# Finger_PPG.net
KiCad netlist of a schematic drawn in EAGLE
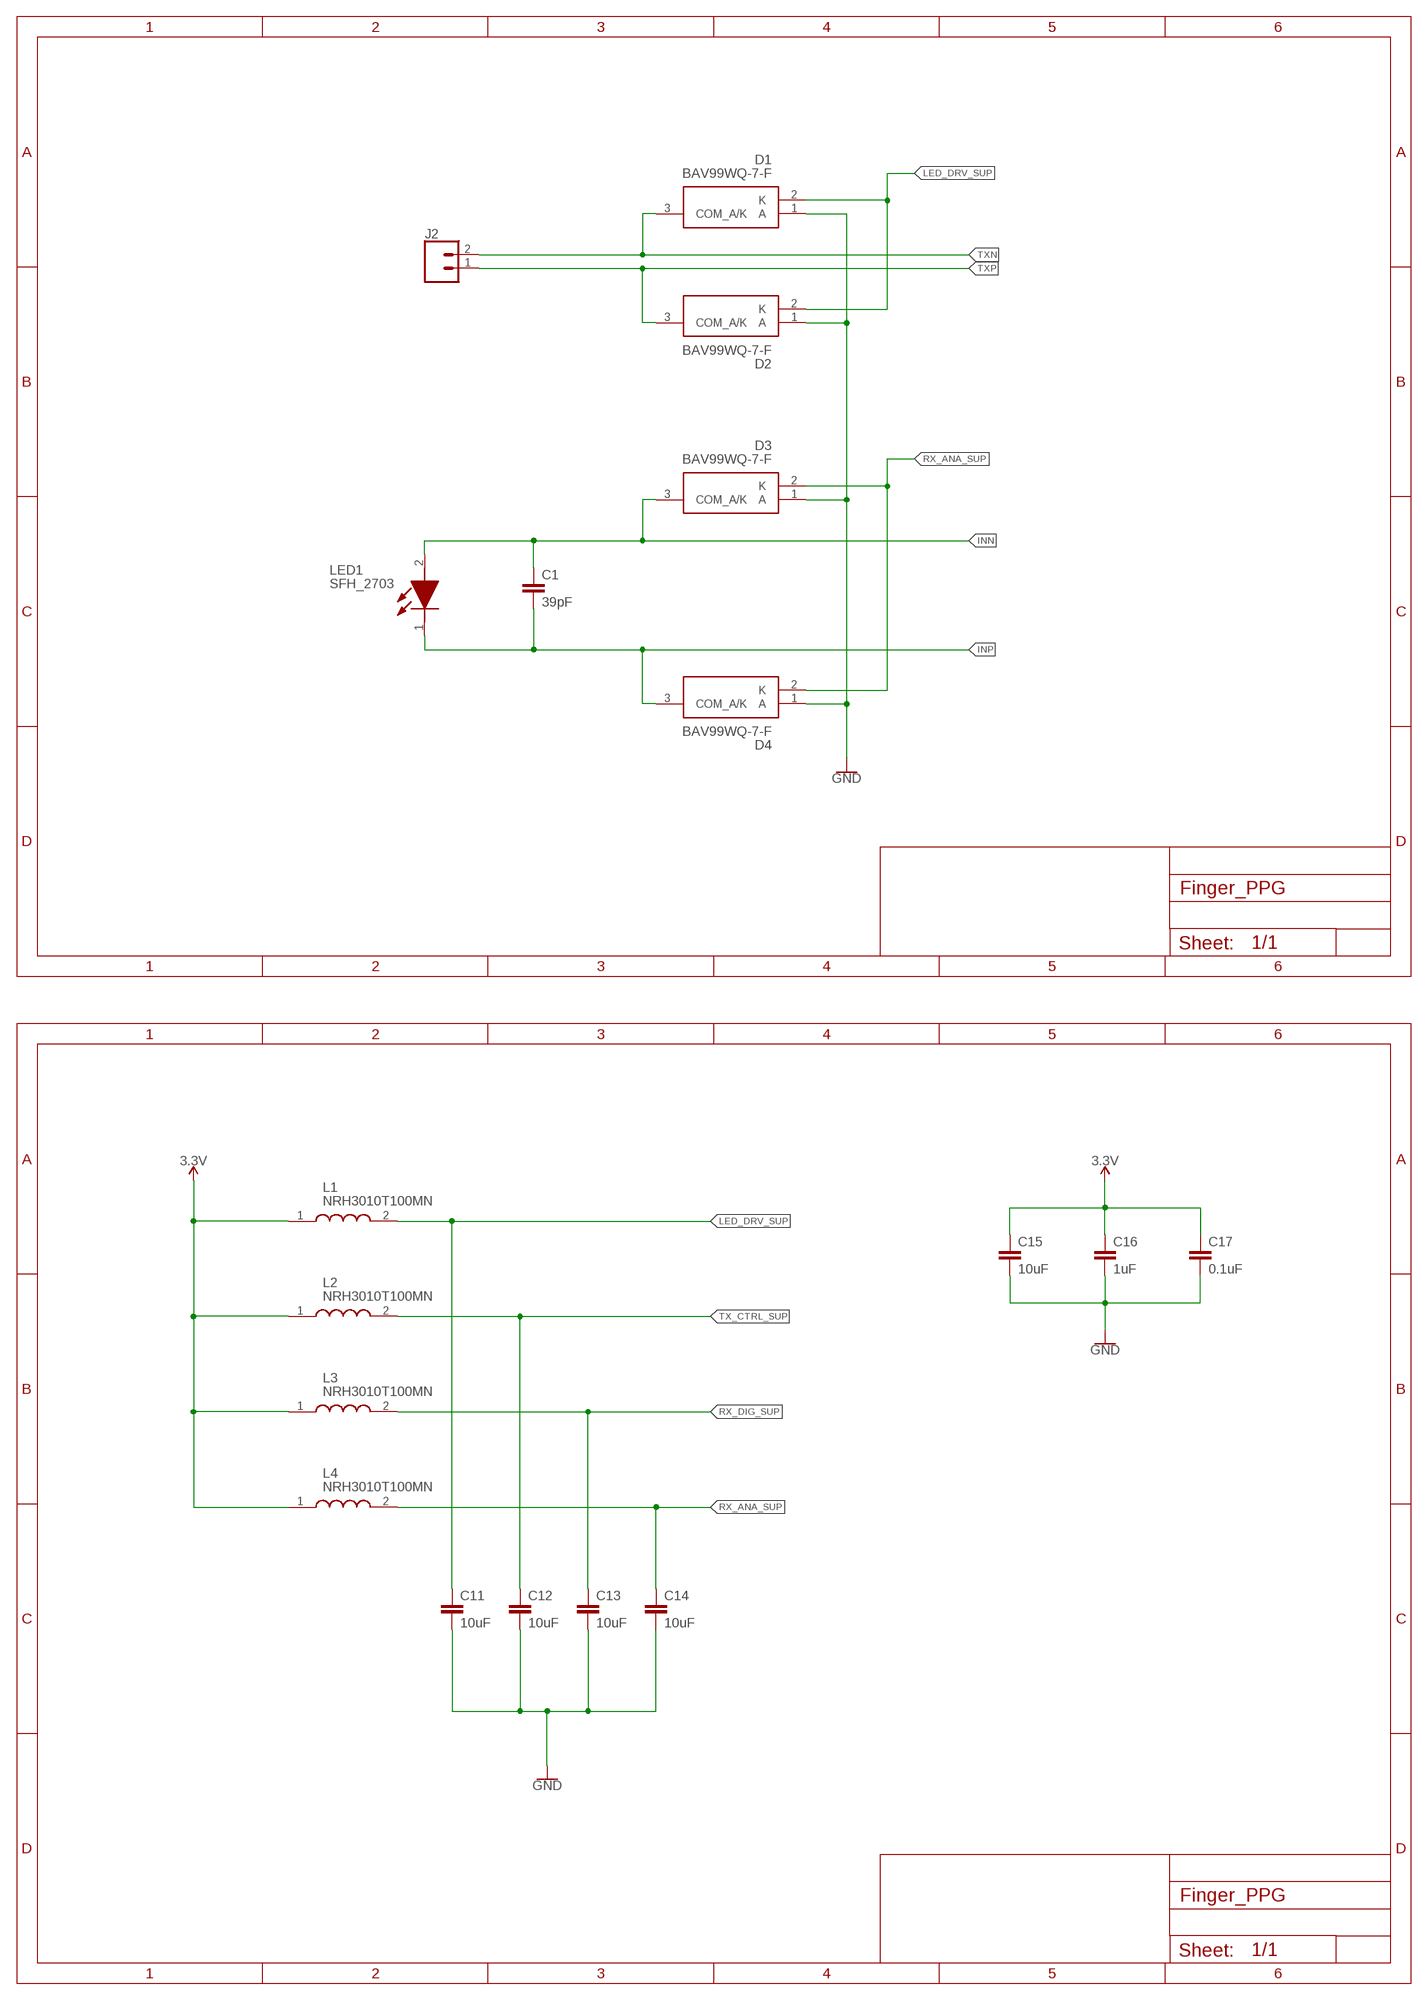
[diagram p0: schematic, sheet 1, part 1 of 2]
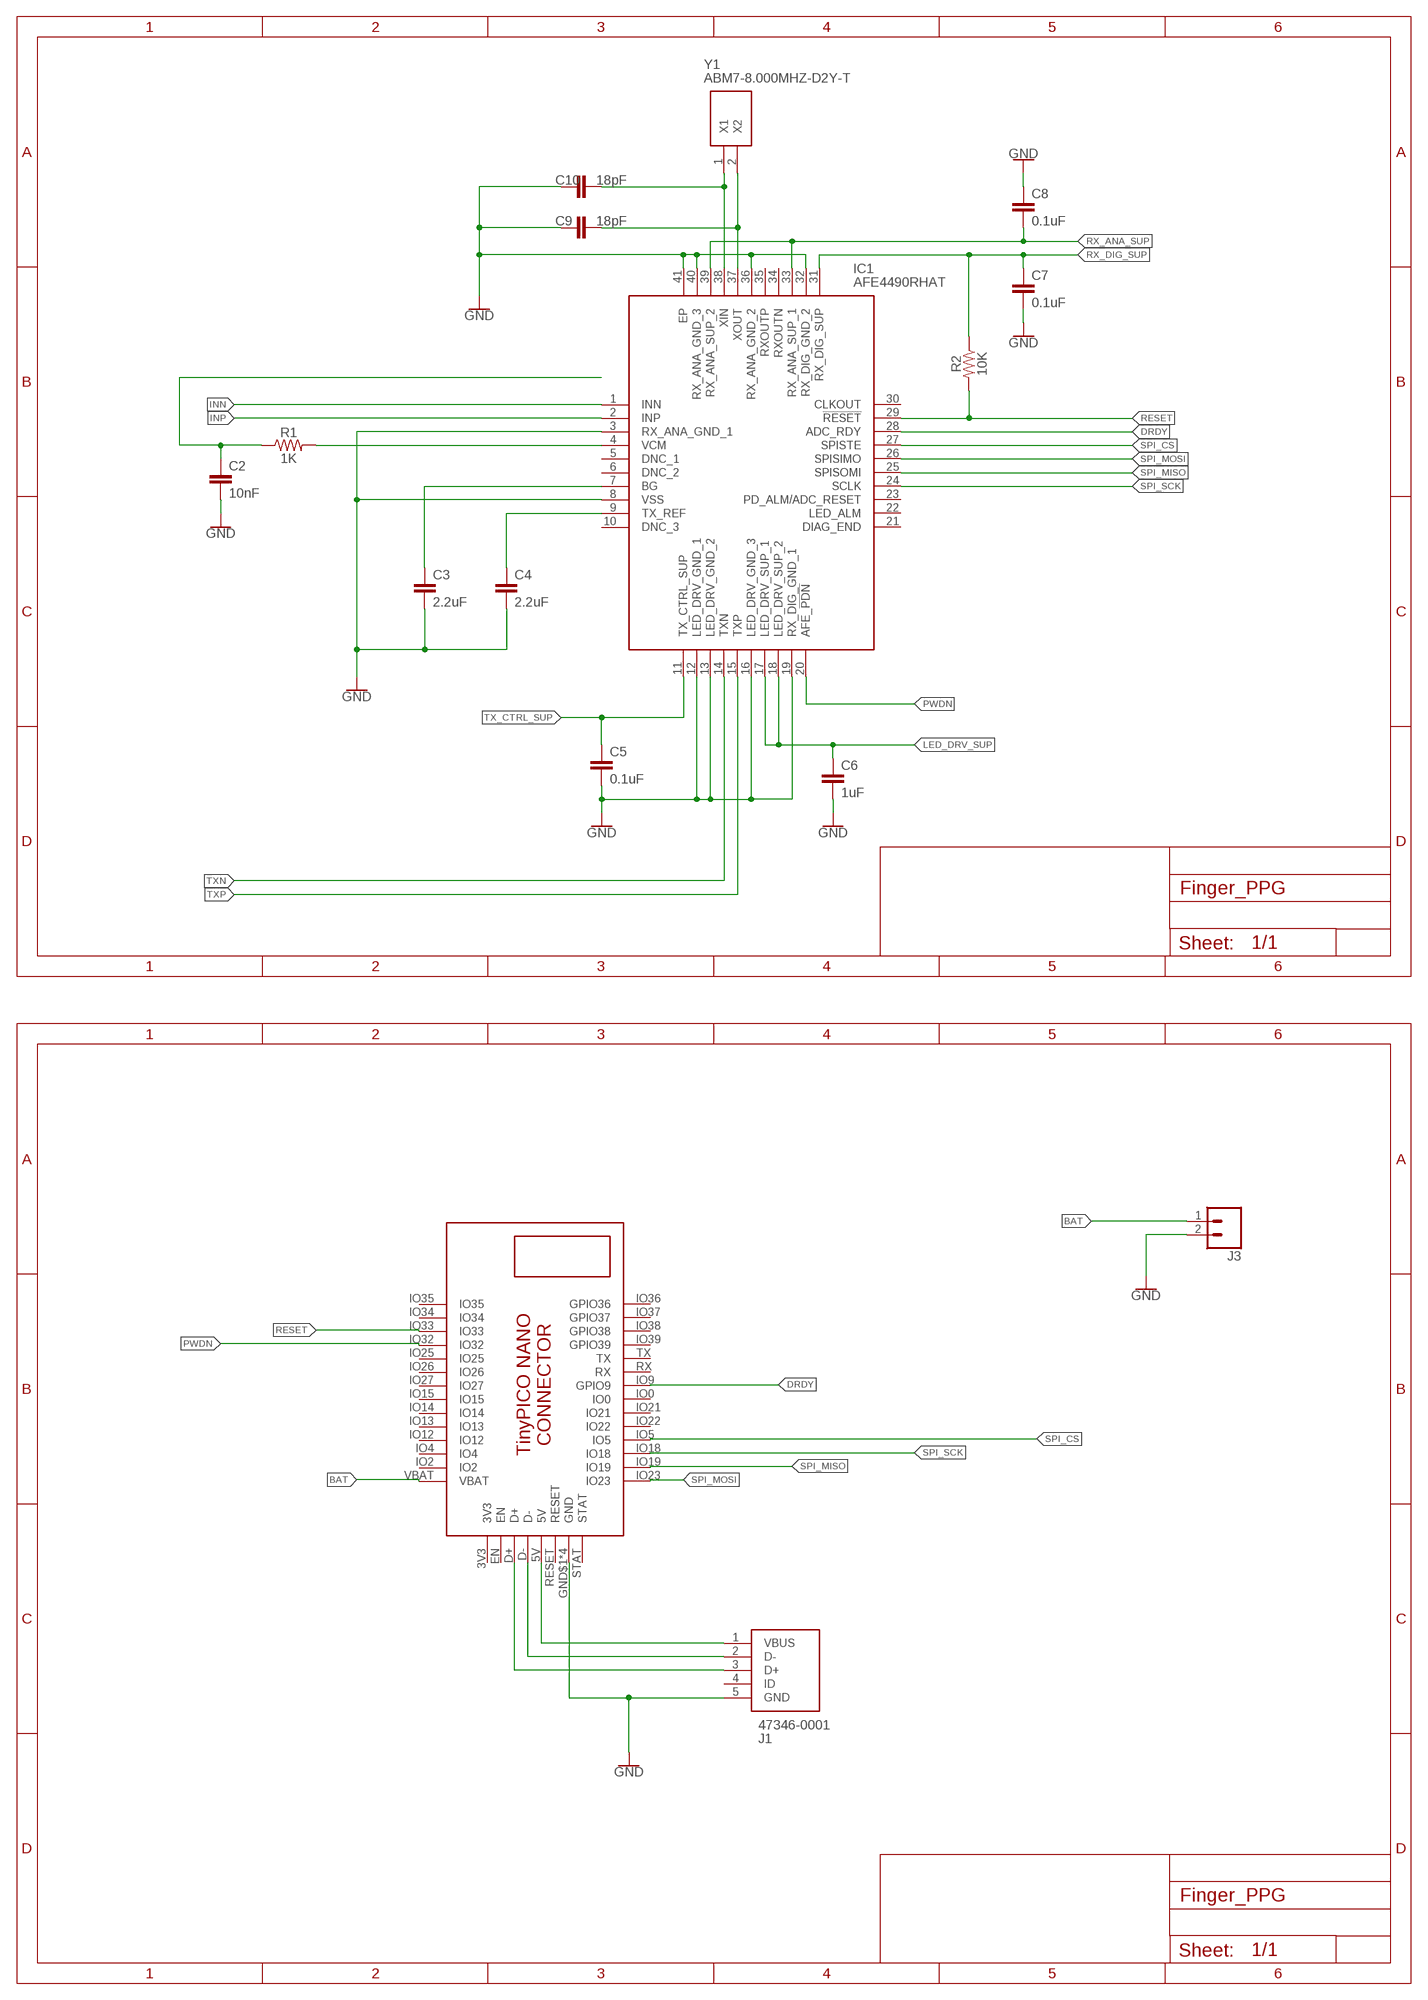
[diagram p1: schematic, sheet 1, part 2 of 2]

(export (version "E")
  (design (tool "Eeschema 10.0.6"))
  (components
    (comp (ref "C1")
      (value "39pF")
      (footprint "eagle-import:0402")
      (libsource (lib "eagle-import") (part "CAP-0402"))
    )
    (comp (ref "C2")
      (value "10nF")
      (footprint "eagle-import:0402")
      (libsource (lib "eagle-import") (part "CAP-0402"))
    )
    (comp (ref "C3")
      (value "2.2uF")
      (footprint "eagle-import:0603")
      (libsource (lib "eagle-import") (part "CAP-0603"))
    )
    (comp (ref "C4")
      (value "2.2uF")
      (footprint "eagle-import:0603")
      (libsource (lib "eagle-import") (part "CAP-0603"))
    )
    (comp (ref "C5")
      (value "0.1uF")
      (footprint "eagle-import:0402")
      (libsource (lib "eagle-import") (part "CAP-0402"))
    )
    (comp (ref "C6")
      (value "1uF")
      (footprint "eagle-import:0402")
      (libsource (lib "eagle-import") (part "CAP-0402"))
    )
    (comp (ref "C7")
      (value "0.1uF")
      (footprint "eagle-import:0402")
      (libsource (lib "eagle-import") (part "CAP-0402"))
    )
    (comp (ref "C8")
      (value "0.1uF")
      (footprint "eagle-import:0402")
      (libsource (lib "eagle-import") (part "CAP-0402"))
    )
    (comp (ref "C9")
      (value "18pF")
      (footprint "eagle-import:0402")
      (libsource (lib "eagle-import") (part "CAP-0402"))
    )
    (comp (ref "C10")
      (value "18pF")
      (footprint "eagle-import:0402")
      (libsource (lib "eagle-import") (part "CAP-0402"))
    )
    (comp (ref "C11")
      (value "10uF")
      (footprint "eagle-import:0805")
      (libsource (lib "eagle-import") (part "CAP-0805"))
    )
    (comp (ref "C12")
      (value "10uF")
      (footprint "eagle-import:0805")
      (libsource (lib "eagle-import") (part "CAP-0805"))
    )
    (comp (ref "C13")
      (value "10uF")
      (footprint "eagle-import:0805")
      (libsource (lib "eagle-import") (part "CAP-0805"))
    )
    (comp (ref "C14")
      (value "10uF")
      (footprint "eagle-import:0805")
      (libsource (lib "eagle-import") (part "CAP-0805"))
    )
    (comp (ref "C15")
      (value "10uF")
      (footprint "eagle-import:0805")
      (libsource (lib "eagle-import") (part "CAP-0805"))
    )
    (comp (ref "C16")
      (value "1uF")
      (footprint "eagle-import:0402")
      (libsource (lib "eagle-import") (part "CAP-0402"))
    )
    (comp (ref "C17")
      (value "0.1uF")
      (footprint "eagle-import:0402")
      (libsource (lib "eagle-import") (part "CAP-0402"))
    )
    (comp (ref "D1")
      (value "BAV99WQ-7-F")
      (footprint "eagle-import:SOT65P210X110-3N")
      (fields (field (name "MOUSER_PART_NUMBER") "621-BAV99WQ-7-F"))
      (libsource (lib "eagle-import") (part "BAV99WQ-7-F"))
    )
    (comp (ref "D2")
      (value "BAV99WQ-7-F")
      (footprint "eagle-import:SOT65P210X110-3N")
      (fields (field (name "MOUSER_PART_NUMBER") "621-BAV99WQ-7-F"))
      (libsource (lib "eagle-import") (part "BAV99WQ-7-F"))
    )
    (comp (ref "D3")
      (value "BAV99WQ-7-F")
      (footprint "eagle-import:SOT65P210X110-3N")
      (fields (field (name "MOUSER_PART_NUMBER") "621-BAV99WQ-7-F"))
      (libsource (lib "eagle-import") (part "BAV99WQ-7-F"))
    )
    (comp (ref "D4")
      (value "BAV99WQ-7-F")
      (footprint "eagle-import:SOT65P210X110-3N")
      (fields (field (name "MOUSER_PART_NUMBER") "621-BAV99WQ-7-F"))
      (libsource (lib "eagle-import") (part "BAV99WQ-7-F"))
    )
    (comp (ref "IC1")
      (value "AFE4490RHAT")
      (footprint "eagle-import:QFN50P600X600X100-41N")
      (fields (field (name "MOUSER_PART_NUMBER") "595-AFE4490RHAT"))
      (libsource (lib "eagle-import") (part "AFE4490RHAT"))
    )
    (comp (ref "J1")
      (value "47346-0001")
      (footprint "eagle-import:47346-0001")
      (fields (field (name "MOUSER_PART_NUMBER") "538-47346-0001"))
      (libsource (lib "eagle-import") (part "47346-0001"))
    )
    (comp (ref "J2")
      (value "CONN_02")
      (footprint "eagle-import:1X02")
      (libsource (lib "eagle-import") (part "CONN_02"))
    )
    (comp (ref "J3")
      (value "CONN_02")
      (footprint "eagle-import:1X02")
      (libsource (lib "eagle-import") (part "CONN_02"))
    )
    (comp (ref "L1")
      (value "NRH3010T100MN")
      (footprint "eagle-import:NRH3010T100MN")
      (fields (field (name "MOUSER_PART_NUMBER") "963-NRH3010T100MN"))
      (libsource (lib "eagle-import") (part "NRH3010T100MN"))
    )
    (comp (ref "L2")
      (value "NRH3010T100MN")
      (footprint "eagle-import:NRH3010T100MN")
      (fields (field (name "MOUSER_PART_NUMBER") "963-NRH3010T100MN"))
      (libsource (lib "eagle-import") (part "NRH3010T100MN"))
    )
    (comp (ref "L3")
      (value "NRH3010T100MN")
      (footprint "eagle-import:NRH3010T100MN")
      (fields (field (name "MOUSER_PART_NUMBER") "963-NRH3010T100MN"))
      (libsource (lib "eagle-import") (part "NRH3010T100MN"))
    )
    (comp (ref "L4")
      (value "NRH3010T100MN")
      (footprint "eagle-import:NRH3010T100MN")
      (fields (field (name "MOUSER_PART_NUMBER") "963-NRH3010T100MN"))
      (libsource (lib "eagle-import") (part "NRH3010T100MN"))
    )
    (comp (ref "LED1")
      (value "SFH_2703")
      (footprint "eagle-import:SFH2703")
      (fields
        (field (name "MANUFACTURER_PART_NUMBER") "SFH 2703")
        (field (name "MOUSER_PART_NUMBER") "720-SFH2703")
      )
      (libsource (lib "eagle-import") (part "SFH_2703"))
    )
    (comp (ref "R1")
      (value "1K")
      (footprint "eagle-import:0402")
      (libsource (lib "eagle-import") (part "RESISTOR0402"))
    )
    (comp (ref "R2")
      (value "10K")
      (footprint "eagle-import:0402")
      (libsource (lib "eagle-import") (part "RESISTOR0402"))
    )
    (comp (ref "U$1")
      (value "TINYPICO-NANO-CONNECTOR")
      (footprint "eagle-import:TINYPICO-NANO-CONNECTOR")
      (libsource (lib "eagle-import") (part "TINYPICO-NANO-CONNECTOR"))
    )
    (comp (ref "Y1")
      (value "ABM7-8.000MHZ-D2Y-T")
      (footprint "eagle-import:ABM78000MHZD2YT")
      (fields (field (name "MOUSER_PART_NUMBER") "815-ABM7-8-D2Y-T"))
      (libsource (lib "eagle-import") (part "ABM7-8.000MHZ-D2Y-T"))
    )
  )
  (nets
    (net (code "1") (name "/3V3") (class "Default")
      (node (ref "U$1") (pin "3V3") (pinfunction "3V3_3V3") (pintype "power_in"))
    )
    (net (code "2") (name "3.3V") (class "Default")
      (node (ref "C15") (pin "1") (pinfunction "1_1") (pintype "passive"))
      (node (ref "C16") (pin "1") (pinfunction "1_1") (pintype "passive"))
      (node (ref "C17") (pin "1") (pinfunction "1_1") (pintype "passive"))
      (node (ref "L1") (pin "1") (pinfunction "1_1") (pintype "bidirectional"))
      (node (ref "L2") (pin "1") (pinfunction "1_1") (pintype "bidirectional"))
      (node (ref "L3") (pin "1") (pinfunction "1_1") (pintype "bidirectional"))
      (node (ref "L4") (pin "1") (pinfunction "1_1") (pintype "bidirectional"))
    )
    (net (code "3") (name "BAT") (class "Default")
      (node (ref "J3") (pin "1") (pinfunction "1_1") (pintype "passive"))
      (node (ref "U$1") (pin "VBAT") (pinfunction "VBAT_VBAT") (pintype "power_in"))
    )
    (net (code "4") (name "DRDY") (class "Default")
      (node (ref "IC1") (pin "28") (pinfunction "ADC_RDY_28") (pintype "bidirectional"))
      (node (ref "U$1") (pin "IO9") (pinfunction "GPIO9_IO9") (pintype "bidirectional"))
    )
    (net (code "5") (name "GND") (class "Default")
      (node (ref "C10") (pin "1") (pinfunction "1_1") (pintype "passive"))
      (node (ref "C11") (pin "2") (pinfunction "2_2") (pintype "passive"))
      (node (ref "C12") (pin "2") (pinfunction "2_2") (pintype "passive"))
      (node (ref "C13") (pin "2") (pinfunction "2_2") (pintype "passive"))
      (node (ref "C14") (pin "2") (pinfunction "2_2") (pintype "passive"))
      (node (ref "C15") (pin "2") (pinfunction "2_2") (pintype "passive"))
      (node (ref "C16") (pin "2") (pinfunction "2_2") (pintype "passive"))
      (node (ref "C17") (pin "2") (pinfunction "2_2") (pintype "passive"))
      (node (ref "C2") (pin "2") (pinfunction "2_2") (pintype "passive"))
      (node (ref "C3") (pin "2") (pinfunction "2_2") (pintype "passive"))
      (node (ref "C4") (pin "2") (pinfunction "2_2") (pintype "passive"))
      (node (ref "C5") (pin "2") (pinfunction "2_2") (pintype "passive"))
      (node (ref "C6") (pin "2") (pinfunction "2_2") (pintype "passive"))
      (node (ref "C7") (pin "2") (pinfunction "2_2") (pintype "passive"))
      (node (ref "C8") (pin "1") (pinfunction "1_1") (pintype "passive"))
      (node (ref "C9") (pin "1") (pinfunction "1_1") (pintype "passive"))
      (node (ref "D1") (pin "1") (pinfunction "A_1") (pintype "bidirectional"))
      (node (ref "D2") (pin "1") (pinfunction "A_1") (pintype "bidirectional"))
      (node (ref "D3") (pin "1") (pinfunction "A_1") (pintype "bidirectional"))
      (node (ref "D4") (pin "1") (pinfunction "A_1") (pintype "bidirectional"))
      (node (ref "IC1") (pin "12") (pinfunction "LED_DRV_GND_1_12") (pintype "bidirectional"))
      (node (ref "IC1") (pin "13") (pinfunction "LED_DRV_GND_2_13") (pintype "bidirectional"))
      (node (ref "IC1") (pin "16") (pinfunction "LED_DRV_GND_3_16") (pintype "bidirectional"))
      (node (ref "IC1") (pin "19") (pinfunction "RX_DIG_GND_1_19") (pintype "bidirectional"))
      (node (ref "IC1") (pin "3") (pinfunction "RX_ANA_GND_1_3") (pintype "bidirectional"))
      (node (ref "IC1") (pin "32") (pinfunction "RX_DIG_GND_2_32") (pintype "bidirectional"))
      (node (ref "IC1") (pin "36") (pinfunction "RX_ANA_GND_2_36") (pintype "bidirectional"))
      (node (ref "IC1") (pin "40") (pinfunction "RX_ANA_GND_3_40") (pintype "bidirectional"))
      (node (ref "IC1") (pin "41") (pinfunction "EP_41") (pintype "bidirectional"))
      (node (ref "IC1") (pin "8") (pinfunction "VSS_8") (pintype "bidirectional"))
      (node (ref "J1") (pin "5") (pinfunction "GND_5") (pintype "bidirectional"))
      (node (ref "J3") (pin "2") (pinfunction "2_2") (pintype "passive"))
      (node (ref "U$1") (pin "GND$1") (pinfunction "GND_GND$1") (pintype "power_in"))
      (node (ref "U$1") (pin "GND$2") (pinfunction "GND_GND$2") (pintype "power_in"))
      (node (ref "U$1") (pin "GND$3") (pinfunction "GND_GND$3") (pintype "power_in"))
      (node (ref "U$1") (pin "GND$4") (pinfunction "GND_GND$4") (pintype "power_in"))
    )
    (net (code "6") (name "INN") (class "Default")
      (node (ref "C1") (pin "1") (pinfunction "1_1") (pintype "passive"))
      (node (ref "D3") (pin "3") (pinfunction "COM_A/K_3") (pintype "bidirectional"))
      (node (ref "IC1") (pin "1") (pinfunction "INN_1") (pintype "bidirectional"))
      (node (ref "LED1") (pin "2") (pinfunction "A_2") (pintype "bidirectional"))
    )
    (net (code "7") (name "INP") (class "Default")
      (node (ref "C1") (pin "2") (pinfunction "2_2") (pintype "passive"))
      (node (ref "D4") (pin "3") (pinfunction "COM_A/K_3") (pintype "bidirectional"))
      (node (ref "IC1") (pin "2") (pinfunction "INP_2") (pintype "bidirectional"))
      (node (ref "LED1") (pin "1") (pinfunction "K_1") (pintype "bidirectional"))
    )
    (net (code "8") (name "LED_DRV_SUP") (class "Default")
      (node (ref "C11") (pin "1") (pinfunction "1_1") (pintype "passive"))
      (node (ref "C6") (pin "1") (pinfunction "1_1") (pintype "passive"))
      (node (ref "D1") (pin "2") (pinfunction "K_2") (pintype "bidirectional"))
      (node (ref "D2") (pin "2") (pinfunction "K_2") (pintype "bidirectional"))
      (node (ref "IC1") (pin "17") (pinfunction "LED_DRV_SUP_1_17") (pintype "bidirectional"))
      (node (ref "IC1") (pin "18") (pinfunction "LED_DRV_SUP_2_18") (pintype "bidirectional"))
      (node (ref "L1") (pin "2") (pinfunction "2_2") (pintype "bidirectional"))
    )
    (net (code "9") (name "Net-(C2-Pad1)") (class "Default")
      (node (ref "C2") (pin "1") (pinfunction "1_1") (pintype "passive"))
      (node (ref "R1") (pin "1") (pinfunction "1_1") (pintype "passive"))
    )
    (net (code "10") (name "Net-(IC1-BG)") (class "Default")
      (node (ref "C3") (pin "1") (pinfunction "1_1") (pintype "passive"))
      (node (ref "IC1") (pin "7") (pinfunction "BG_7") (pintype "bidirectional"))
    )
    (net (code "11") (name "Net-(IC1-TX_REF)") (class "Default")
      (node (ref "C4") (pin "1") (pinfunction "1_1") (pintype "passive"))
      (node (ref "IC1") (pin "9") (pinfunction "TX_REF_9") (pintype "bidirectional"))
    )
    (net (code "12") (name "Net-(IC1-VCM)") (class "Default")
      (node (ref "IC1") (pin "4") (pinfunction "VCM_4") (pintype "bidirectional"))
      (node (ref "R1") (pin "2") (pinfunction "2_2") (pintype "passive"))
    )
    (net (code "13") (name "Net-(IC1-XIN)") (class "Default")
      (node (ref "C10") (pin "2") (pinfunction "2_2") (pintype "passive"))
      (node (ref "IC1") (pin "38") (pinfunction "XIN_38") (pintype "bidirectional"))
      (node (ref "Y1") (pin "1") (pinfunction "X1_1") (pintype "bidirectional"))
    )
    (net (code "14") (name "Net-(IC1-XOUT)") (class "Default")
      (node (ref "C9") (pin "2") (pinfunction "2_2") (pintype "passive"))
      (node (ref "IC1") (pin "37") (pinfunction "XOUT_37") (pintype "bidirectional"))
      (node (ref "Y1") (pin "2") (pinfunction "X2_2") (pintype "bidirectional"))
    )
    (net (code "15") (name "Net-(J1-D+)") (class "Default")
      (node (ref "J1") (pin "3") (pinfunction "D+_3") (pintype "bidirectional"))
      (node (ref "U$1") (pin "D+") (pinfunction "D+_D+") (pintype "bidirectional"))
    )
    (net (code "16") (name "Net-(J1-D-)") (class "Default")
      (node (ref "J1") (pin "2") (pinfunction "D-_2") (pintype "bidirectional"))
      (node (ref "U$1") (pin "D-") (pinfunction "D-_D-") (pintype "bidirectional"))
    )
    (net (code "17") (name "Net-(J1-VBUS)") (class "Default")
      (node (ref "J1") (pin "1") (pinfunction "VBUS_1") (pintype "bidirectional"))
      (node (ref "U$1") (pin "5V") (pinfunction "5V_5V") (pintype "power_in"))
    )
    (net (code "18") (name "PWDN") (class "Default")
      (node (ref "IC1") (pin "20") (pinfunction "AFE_~{PDN}_20") (pintype "bidirectional"))
      (node (ref "U$1") (pin "IO32") (pinfunction "IO32_IO32") (pintype "bidirectional"))
    )
    (net (code "19") (name "RESET") (class "Default")
      (node (ref "IC1") (pin "29") (pinfunction "~{RESET}_29") (pintype "bidirectional"))
      (node (ref "R2") (pin "2") (pinfunction "2_2") (pintype "passive"))
      (node (ref "U$1") (pin "IO33") (pinfunction "IO33_IO33") (pintype "bidirectional"))
    )
    (net (code "20") (name "RX_ANA_SUP") (class "Default")
      (node (ref "C14") (pin "1") (pinfunction "1_1") (pintype "passive"))
      (node (ref "C8") (pin "2") (pinfunction "2_2") (pintype "passive"))
      (node (ref "D3") (pin "2") (pinfunction "K_2") (pintype "bidirectional"))
      (node (ref "D4") (pin "2") (pinfunction "K_2") (pintype "bidirectional"))
      (node (ref "IC1") (pin "33") (pinfunction "RX_ANA_SUP_1_33") (pintype "bidirectional"))
      (node (ref "IC1") (pin "39") (pinfunction "RX_ANA_SUP_2_39") (pintype "bidirectional"))
      (node (ref "L4") (pin "2") (pinfunction "2_2") (pintype "bidirectional"))
    )
    (net (code "21") (name "RX_DIG_SUP") (class "Default")
      (node (ref "C13") (pin "1") (pinfunction "1_1") (pintype "passive"))
      (node (ref "C7") (pin "1") (pinfunction "1_1") (pintype "passive"))
      (node (ref "IC1") (pin "31") (pinfunction "RX_DIG_SUP_31") (pintype "bidirectional"))
      (node (ref "L3") (pin "2") (pinfunction "2_2") (pintype "bidirectional"))
      (node (ref "R2") (pin "1") (pinfunction "1_1") (pintype "passive"))
    )
    (net (code "22") (name "SPI_CS") (class "Default")
      (node (ref "IC1") (pin "27") (pinfunction "SPISTE_27") (pintype "bidirectional"))
      (node (ref "U$1") (pin "IO5") (pinfunction "IO5_IO5") (pintype "bidirectional"))
    )
    (net (code "23") (name "SPI_MISO") (class "Default")
      (node (ref "IC1") (pin "25") (pinfunction "SPISOMI_25") (pintype "bidirectional"))
      (node (ref "U$1") (pin "IO19") (pinfunction "IO19_IO19") (pintype "bidirectional"))
    )
    (net (code "24") (name "SPI_MOSI") (class "Default")
      (node (ref "IC1") (pin "26") (pinfunction "SPISIMO_26") (pintype "bidirectional"))
      (node (ref "U$1") (pin "IO23") (pinfunction "IO23_IO23") (pintype "bidirectional"))
    )
    (net (code "25") (name "SPI_SCK") (class "Default")
      (node (ref "IC1") (pin "24") (pinfunction "SCLK_24") (pintype "bidirectional"))
      (node (ref "U$1") (pin "IO18") (pinfunction "IO18_IO18") (pintype "bidirectional"))
    )
    (net (code "26") (name "TXN") (class "Default")
      (node (ref "D1") (pin "3") (pinfunction "COM_A/K_3") (pintype "bidirectional"))
      (node (ref "IC1") (pin "14") (pinfunction "TXN_14") (pintype "bidirectional"))
      (node (ref "J2") (pin "2") (pinfunction "2_2") (pintype "passive"))
    )
    (net (code "27") (name "TXP") (class "Default")
      (node (ref "D2") (pin "3") (pinfunction "COM_A/K_3") (pintype "bidirectional"))
      (node (ref "IC1") (pin "15") (pinfunction "TXP_15") (pintype "bidirectional"))
      (node (ref "J2") (pin "1") (pinfunction "1_1") (pintype "passive"))
    )
    (net (code "28") (name "TX_CTRL_SUP") (class "Default")
      (node (ref "C12") (pin "1") (pinfunction "1_1") (pintype "passive"))
      (node (ref "C5") (pin "1") (pinfunction "1_1") (pintype "passive"))
      (node (ref "IC1") (pin "11") (pinfunction "TX_CTRL_SUP_11") (pintype "bidirectional"))
      (node (ref "L2") (pin "2") (pinfunction "2_2") (pintype "bidirectional"))
    )
    (net (code "29") (name "unconnected-(IC1-CLKOUT-Pad30)") (class "Default")
      (node (ref "IC1") (pin "30") (pinfunction "CLKOUT_30") (pintype "bidirectional"))
    )
    (net (code "30") (name "unconnected-(IC1-DIAG_END-Pad21)") (class "Default")
      (node (ref "IC1") (pin "21") (pinfunction "DIAG_END_21") (pintype "bidirectional"))
    )
    (net (code "31") (name "unconnected-(IC1-DNC_1-Pad5)") (class "Default")
      (node (ref "IC1") (pin "5") (pinfunction "DNC_1_5") (pintype "bidirectional"))
    )
    (net (code "32") (name "unconnected-(IC1-DNC_2-Pad6)") (class "Default")
      (node (ref "IC1") (pin "6") (pinfunction "DNC_2_6") (pintype "bidirectional"))
    )
    (net (code "33") (name "unconnected-(IC1-DNC_3-Pad10)") (class "Default")
      (node (ref "IC1") (pin "10") (pinfunction "DNC_3_10") (pintype "bidirectional"))
    )
    (net (code "34") (name "unconnected-(IC1-LED_ALM-Pad22)") (class "Default")
      (node (ref "IC1") (pin "22") (pinfunction "LED_ALM_22") (pintype "bidirectional"))
    )
    (net (code "35") (name "unconnected-(IC1-PD_ALM{slash}ADC_RESET-Pad23)") (class "Default")
      (node (ref "IC1") (pin "23") (pinfunction "PD_ALM/ADC_RESET_23") (pintype "bidirectional"))
    )
    (net (code "36") (name "unconnected-(IC1-RXOUTN-Pad34)") (class "Default")
      (node (ref "IC1") (pin "34") (pinfunction "RXOUTN_34") (pintype "bidirectional"))
    )
    (net (code "37") (name "unconnected-(IC1-RXOUTP-Pad35)") (class "Default")
      (node (ref "IC1") (pin "35") (pinfunction "RXOUTP_35") (pintype "bidirectional"))
    )
    (net (code "38") (name "unconnected-(J1-ID-Pad4)") (class "Default")
      (node (ref "J1") (pin "4") (pinfunction "ID_4") (pintype "bidirectional"))
    )
    (net (code "39") (name "unconnected-(U$1-GPIO36-PadIO36)") (class "Default")
      (node (ref "U$1") (pin "IO36") (pinfunction "GPIO36_IO36") (pintype "bidirectional"))
    )
    (net (code "40") (name "unconnected-(U$1-GPIO37-PadIO37)") (class "Default")
      (node (ref "U$1") (pin "IO37") (pinfunction "GPIO37_IO37") (pintype "bidirectional"))
    )
    (net (code "41") (name "unconnected-(U$1-GPIO38-PadIO38)") (class "Default")
      (node (ref "U$1") (pin "IO38") (pinfunction "GPIO38_IO38") (pintype "bidirectional"))
    )
    (net (code "42") (name "unconnected-(U$1-GPIO39-PadIO39)") (class "Default")
      (node (ref "U$1") (pin "IO39") (pinfunction "GPIO39_IO39") (pintype "bidirectional"))
    )
    (net (code "43") (name "unconnected-(U$1-PadEN)") (class "Default")
      (node (ref "U$1") (pin "EN") (pinfunction "EN_EN") (pintype "input"))
    )
    (net (code "44") (name "unconnected-(U$1-PadIO0)") (class "Default")
      (node (ref "U$1") (pin "IO0") (pinfunction "IO0_IO0") (pintype "bidirectional"))
    )
    (net (code "45") (name "unconnected-(U$1-PadIO2)") (class "Default")
      (node (ref "U$1") (pin "IO2") (pinfunction "IO2_IO2") (pintype "bidirectional"))
    )
    (net (code "46") (name "unconnected-(U$1-PadIO4)") (class "Default")
      (node (ref "U$1") (pin "IO4") (pinfunction "IO4_IO4") (pintype "bidirectional"))
    )
    (net (code "47") (name "unconnected-(U$1-PadIO12)") (class "Default")
      (node (ref "U$1") (pin "IO12") (pinfunction "IO12_IO12") (pintype "bidirectional"))
    )
    (net (code "48") (name "unconnected-(U$1-PadIO13)") (class "Default")
      (node (ref "U$1") (pin "IO13") (pinfunction "IO13_IO13") (pintype "bidirectional"))
    )
    (net (code "49") (name "unconnected-(U$1-PadIO14)") (class "Default")
      (node (ref "U$1") (pin "IO14") (pinfunction "IO14_IO14") (pintype "bidirectional"))
    )
    (net (code "50") (name "unconnected-(U$1-PadIO15)") (class "Default")
      (node (ref "U$1") (pin "IO15") (pinfunction "IO15_IO15") (pintype "bidirectional"))
    )
    (net (code "51") (name "unconnected-(U$1-PadIO21)") (class "Default")
      (node (ref "U$1") (pin "IO21") (pinfunction "IO21_IO21") (pintype "bidirectional"))
    )
    (net (code "52") (name "unconnected-(U$1-PadIO22)") (class "Default")
      (node (ref "U$1") (pin "IO22") (pinfunction "IO22_IO22") (pintype "bidirectional"))
    )
    (net (code "53") (name "unconnected-(U$1-PadIO25)") (class "Default")
      (node (ref "U$1") (pin "IO25") (pinfunction "IO25_IO25") (pintype "bidirectional"))
    )
    (net (code "54") (name "unconnected-(U$1-PadIO26)") (class "Default")
      (node (ref "U$1") (pin "IO26") (pinfunction "IO26_IO26") (pintype "bidirectional"))
    )
    (net (code "55") (name "unconnected-(U$1-PadIO27)") (class "Default")
      (node (ref "U$1") (pin "IO27") (pinfunction "IO27_IO27") (pintype "bidirectional"))
    )
    (net (code "56") (name "unconnected-(U$1-PadIO34)") (class "Default")
      (node (ref "U$1") (pin "IO34") (pinfunction "IO34_IO34") (pintype "bidirectional"))
    )
    (net (code "57") (name "unconnected-(U$1-PadIO35)") (class "Default")
      (node (ref "U$1") (pin "IO35") (pinfunction "IO35_IO35") (pintype "bidirectional"))
    )
    (net (code "58") (name "unconnected-(U$1-PadRESET)") (class "Default")
      (node (ref "U$1") (pin "RESET") (pinfunction "RESET_RESET") (pintype "bidirectional"))
    )
    (net (code "59") (name "unconnected-(U$1-PadRX)") (class "Default")
      (node (ref "U$1") (pin "RX") (pinfunction "RX_RX") (pintype "bidirectional"))
    )
    (net (code "60") (name "unconnected-(U$1-PadSTAT)") (class "Default")
      (node (ref "U$1") (pin "STAT") (pinfunction "STAT_STAT") (pintype "output"))
    )
    (net (code "61") (name "unconnected-(U$1-PadTX)") (class "Default")
      (node (ref "U$1") (pin "TX") (pinfunction "TX_TX") (pintype "bidirectional"))
    )
  )
)
